# Source.net
KiCad netlist of a schematic drawn in Altium Designer
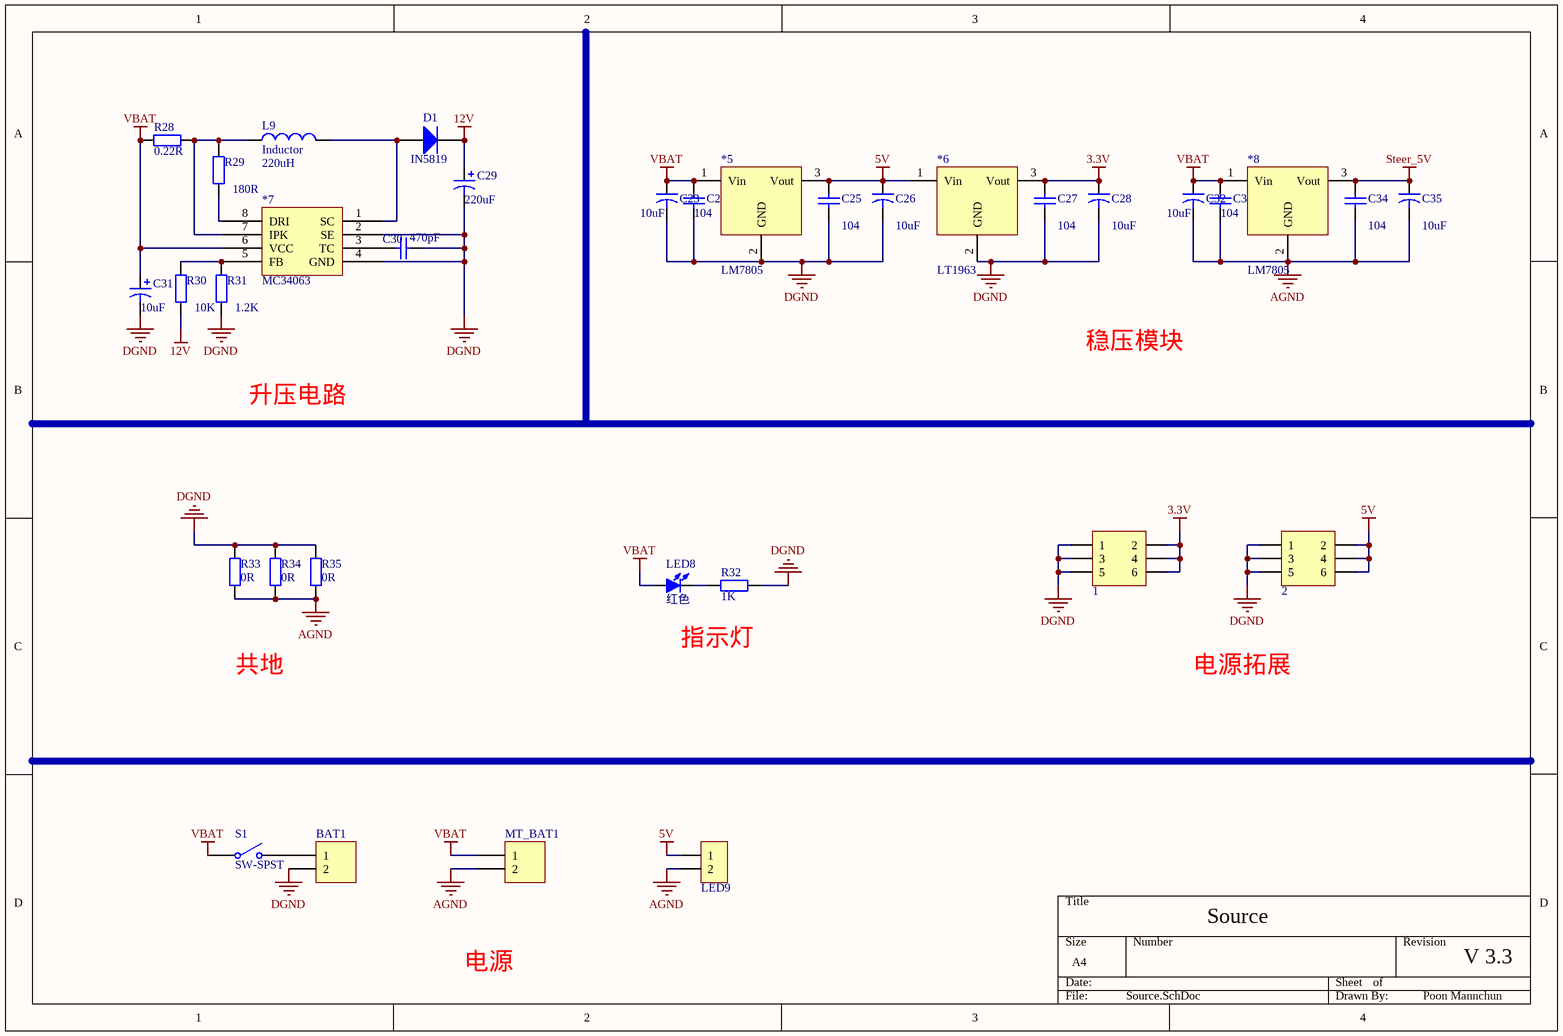
[diagram p0: Source.SchDoc]

(export (version "E")
  (design (tool "Eeschema 10.0.6"))
  (components
    (comp (ref "*5") (value "LM7805") (footprint "SOT223_N") (libsource (lib "LongMen") (part "LM2940")))
    (comp (ref "*6") (value "LT1963") (footprint "SOT223_N") (libsource (lib "LongMen") (part "LM2940")))
    (comp (ref "*7") (value "MC34063") (footprint "SOP8_N") (libsource (lib "MIC5219") (part "MC34063")))
    (comp (ref "*8") (value "LM7805") (footprint "SOT223_N") (libsource (lib "LongMen") (part "LM2940")))
    (comp (ref "1")
      (value "Header3X2")
      (footprint "HDR-3X2")
      (description "3*2P接插件")
      (fields (field (name "版权归属") "源创客"))
      (libsource (lib "接插件") (part "Header 3X2"))
    )
    (comp (ref "2")
      (value "Header3X2")
      (footprint "HDR-3X2")
      (description "3*2P接插件")
      (fields (field (name "版权归属") "源创客"))
      (libsource (lib "接插件") (part "Header 3X2"))
    )
    (comp (ref "BAT1")
      (value "Header 2")
      (footprint "SW - duplicate")
      (description "Header, 2-Pin")
      (fields (field (name "PUBLISHER") "Altium Limited"))
      (libsource (lib "PROJECT") (part "Header 2"))
    )
    (comp (ref "C23")
      (value "10uF")
      (footprint "CD A(3216)")
      (description "Capacitor")
      (fields (field (name "Comment") "Cap2") (field (name "PUBLISHER") "Altium Limited"))
      (libsource (lib "Miscellaneous Devices") (part "Cap2"))
    )
    (comp (ref "C24")
      (value "104")
      (footprint "C 0805_L")
      (description "Capacitor")
      (fields (field (name "PUBLISHER") "Altium Limited"))
      (libsource (lib "Miscellaneous Devices") (part "Cap"))
    )
    (comp (ref "C25")
      (value "104")
      (footprint "C 0805_L")
      (description "Capacitor")
      (fields (field (name "PUBLISHER") "Altium Limited"))
      (libsource (lib "Miscellaneous Devices") (part "Cap"))
    )
    (comp (ref "C26")
      (value "10uF")
      (footprint "CD A(3216)")
      (description "Capacitor")
      (fields (field (name "Comment") "Cap2") (field (name "PUBLISHER") "Altium Limited"))
      (libsource (lib "Miscellaneous Devices") (part "Cap2"))
    )
    (comp (ref "C27")
      (value "104")
      (footprint "C 0805_L")
      (description "Capacitor")
      (fields (field (name "PUBLISHER") "Altium Limited"))
      (libsource (lib "Miscellaneous Devices") (part "Cap"))
    )
    (comp (ref "C28")
      (value "10uF")
      (footprint "CD A(3216)")
      (description "Capacitor")
      (fields (field (name "Comment") "Cap2") (field (name "PUBLISHER") "Altium Limited"))
      (libsource (lib "Miscellaneous Devices") (part "Cap2"))
    )
    (comp (ref "C29")
      (value "220uF")
      (footprint "CD B(3528)")
      (description "Polarized Capacitor (Radial)")
      (fields (field (name "Comment") "Cap Pol1") (field (name "PUBLISHER") "Altium Limited"))
      (libsource (lib "Miscellaneous Devices") (part "Cap Pol1"))
    )
    (comp (ref "C30")
      (value "470pF")
      (footprint "C 0805_L")
      (description "Capacitor")
      (fields (field (name "Comment") "Cap") (field (name "PUBLISHER") "Altium Limited"))
      (libsource (lib "Miscellaneous Devices") (part "Cap"))
    )
    (comp (ref "C31")
      (value "10uF")
      (footprint "CD A(3216)")
      (description "Polarized Capacitor (Radial)")
      (fields (field (name "Comment") "Cap Pol1") (field (name "PUBLISHER") "Altium Limited"))
      (libsource (lib "Miscellaneous Devices") (part "Cap Pol1"))
    )
    (comp (ref "C32")
      (value "10uF")
      (footprint "CD A(3216)")
      (description "Capacitor")
      (fields (field (name "Comment") "Cap2") (field (name "PUBLISHER") "Altium Limited"))
      (libsource (lib "Miscellaneous Devices") (part "Cap2"))
    )
    (comp (ref "C33")
      (value "104")
      (footprint "C 0805_L")
      (description "Capacitor")
      (fields (field (name "PUBLISHER") "Altium Limited"))
      (libsource (lib "Miscellaneous Devices") (part "Cap"))
    )
    (comp (ref "C34")
      (value "104")
      (footprint "C 0805_L")
      (description "Capacitor")
      (fields (field (name "PUBLISHER") "Altium Limited"))
      (libsource (lib "Miscellaneous Devices") (part "Cap"))
    )
    (comp (ref "C35")
      (value "10uF")
      (footprint "CD A(3216)")
      (description "Capacitor")
      (fields (field (name "Comment") "Cap2") (field (name "PUBLISHER") "Altium Limited"))
      (libsource (lib "Miscellaneous Devices") (part "Cap2"))
    )
    (comp (ref "D1")
      (value "IN5819")
      (footprint "SMA")
      (description "Default Diode")
      (fields (field (name "PUBLISHER") "Altium Limited"))
      (libsource (lib "Miscellaneous Devices") (part "Diode"))
    )
    (comp (ref "L9")
      (value "Inductor")
      (footprint "CDRH124")
      (fields (field (name "ALTIUM_VALUE") "220uH") (field (name "PUBLISHER") "Altium Limited"))
      (libsource (lib "Miscellaneous Devices") (part "Inductor"))
    )
    (comp (ref "LED8")
      (value "红色")
      (footprint "LED 0805R")
      (description "贴片LED")
      (fields (field (name "版权归属") "源创客"))
      (libsource (lib "LED") (part "LED-SMD"))
    )
    (comp (ref "LED9")
      (value "HDR-1X2")
      (footprint "HDR-1X2")
      (description "2P接插件")
      (fields (field (name "版权归属") "源创客"))
      (libsource (lib "接插件") (part "Header 2"))
    )
    (comp (ref "MT_BAT1")
      (value "Header 2")
      (footprint "SW - duplicate")
      (description "Header, 2-Pin")
      (fields (field (name "PUBLISHER") "Altium Limited"))
      (libsource (lib "PROJECT") (part "Header 2"))
    )
    (comp (ref "R28")
      (value "0.22R")
      (footprint "R 0805_L")
      (description "Resistor")
      (fields (field (name "Comment") "Res2") (field (name "PUBLISHER") "Altium Limited"))
      (libsource (lib "") (part "Res2_2"))
    )
    (comp (ref "R29")
      (value "180R")
      (footprint "R 0805_L")
      (description "Resistor")
      (fields (field (name "Comment") "Res2") (field (name "PUBLISHER") "Altium Limited"))
      (libsource (lib "") (part "Res2_1"))
    )
    (comp (ref "R30")
      (value "10K")
      (footprint "R 0805_L")
      (description "Resistor")
      (fields (field (name "Comment") "Res2") (field (name "PUBLISHER") "Altium Limited"))
      (libsource (lib "") (part "Res2_1"))
    )
    (comp (ref "R31")
      (value "1.2K")
      (footprint "R 0805_L")
      (description "Resistor")
      (fields (field (name "Comment") "Res2") (field (name "PUBLISHER") "Altium Limited"))
      (libsource (lib "") (part "Res2_1"))
    )
    (comp (ref "R32")
      (value "1K")
      (footprint "R 0805_L")
      (description "Resistor")
      (fields (field (name "PUBLISHER") "Altium Limited"))
      (libsource (lib "6-MK60DN512VLL10核心板") (part "Res2"))
    )
    (comp (ref "R33")
      (value "0R")
      (footprint "R 0805_L")
      (description "Resistor")
      (fields (field (name "Comment") "Res2") (field (name "PUBLISHER") "Altium Limited"))
      (libsource (lib "Miscellaneous Devices") (part "Res2"))
    )
    (comp (ref "R34")
      (value "0R")
      (footprint "R 0805_L")
      (description "Resistor")
      (fields (field (name "Comment") "Res2") (field (name "PUBLISHER") "Altium Limited"))
      (libsource (lib "Miscellaneous Devices") (part "Res2"))
    )
    (comp (ref "R35")
      (value "0R")
      (footprint "R 0805_L")
      (description "Resistor")
      (fields (field (name "Comment") "Res2") (field (name "PUBLISHER") "Altium Limited"))
      (libsource (lib "Miscellaneous Devices") (part "Res2"))
    )
    (comp (ref "S1")
      (value "SW-SPST")
      (footprint "MTS-10x")
      (description "Single-Pole, Single-Throw Switch")
      (fields (field (name "PUBLISHER") "Altium Limited"))
      (libsource (lib "Miscellaneous Devices") (part "SW-SPST"))
    )
  )
  (nets
    (net (code "1") (name "3.3V") (class "Default")
      (node (ref "*6") (pin "3") (pinfunction "Vout_3") (pintype "passive"))
      (node (ref "1") (pin "2") (pinfunction "2_2") (pintype "passive"))
      (node (ref "1") (pin "4") (pinfunction "4_4") (pintype "passive"))
      (node (ref "1") (pin "6") (pinfunction "6_6") (pintype "passive"))
      (node (ref "C27") (pin "2") (pinfunction "2_2") (pintype "passive"))
      (node (ref "C28") (pin "1") (pinfunction "1_1") (pintype "passive"))
    )
    (net (code "2") (name "5V") (class "Default")
      (node (ref "*5") (pin "3") (pinfunction "Vout_3") (pintype "passive"))
      (node (ref "*6") (pin "1") (pinfunction "Vin_1") (pintype "passive"))
      (node (ref "2") (pin "2") (pinfunction "2_2") (pintype "passive"))
      (node (ref "2") (pin "4") (pinfunction "4_4") (pintype "passive"))
      (node (ref "2") (pin "6") (pinfunction "6_6") (pintype "passive"))
      (node (ref "C25") (pin "2") (pinfunction "2_2") (pintype "passive"))
      (node (ref "C26") (pin "1") (pinfunction "1_1") (pintype "passive"))
      (node (ref "LED9") (pin "1") (pinfunction "1_1") (pintype "passive"))
    )
    (net (code "3") (name "12V") (class "Default")
      (node (ref "C29") (pin "1") (pinfunction "1_1") (pintype "passive"))
      (node (ref "D1") (pin "2") (pinfunction "K_2") (pintype "passive"))
      (node (ref "R30") (pin "1") (pinfunction "1_1") (pintype "passive"))
    )
    (net (code "4") (name "AGND") (class "Default")
      (node (ref "*8") (pin "2") (pinfunction "GND_2") (pintype "passive"))
      (node (ref "C32") (pin "2") (pinfunction "2_2") (pintype "passive"))
      (node (ref "C33") (pin "1") (pinfunction "1_1") (pintype "passive"))
      (node (ref "C34") (pin "1") (pinfunction "1_1") (pintype "passive"))
      (node (ref "C35") (pin "2") (pinfunction "2_2") (pintype "passive"))
      (node (ref "LED9") (pin "2") (pinfunction "2_2") (pintype "passive"))
      (node (ref "MT_BAT1") (pin "2") (pinfunction "2_2") (pintype "passive"))
      (node (ref "R33") (pin "2") (pinfunction "2_2") (pintype "passive"))
      (node (ref "R34") (pin "2") (pinfunction "2_2") (pintype "passive"))
      (node (ref "R35") (pin "2") (pinfunction "2_2") (pintype "passive"))
    )
    (net (code "5") (name "DGND") (class "Default")
      (node (ref "*5") (pin "2") (pinfunction "GND_2") (pintype "passive"))
      (node (ref "*6") (pin "2") (pinfunction "GND_2") (pintype "passive"))
      (node (ref "*7") (pin "2") (pinfunction "SE_2") (pintype "passive"))
      (node (ref "*7") (pin "4") (pinfunction "GND_4") (pintype "passive"))
      (node (ref "1") (pin "1") (pinfunction "1_1") (pintype "passive"))
      (node (ref "1") (pin "3") (pinfunction "3_3") (pintype "passive"))
      (node (ref "1") (pin "5") (pinfunction "5_5") (pintype "passive"))
      (node (ref "2") (pin "1") (pinfunction "1_1") (pintype "passive"))
      (node (ref "2") (pin "3") (pinfunction "3_3") (pintype "passive"))
      (node (ref "2") (pin "5") (pinfunction "5_5") (pintype "passive"))
      (node (ref "BAT1") (pin "2") (pinfunction "2_2") (pintype "passive"))
      (node (ref "C23") (pin "2") (pinfunction "2_2") (pintype "passive"))
      (node (ref "C24") (pin "1") (pinfunction "1_1") (pintype "passive"))
      (node (ref "C25") (pin "1") (pinfunction "1_1") (pintype "passive"))
      (node (ref "C26") (pin "2") (pinfunction "2_2") (pintype "passive"))
      (node (ref "C27") (pin "1") (pinfunction "1_1") (pintype "passive"))
      (node (ref "C28") (pin "2") (pinfunction "2_2") (pintype "passive"))
      (node (ref "C29") (pin "2") (pinfunction "2_2") (pintype "passive"))
      (node (ref "C30") (pin "2") (pinfunction "2_2") (pintype "passive"))
      (node (ref "C31") (pin "2") (pinfunction "2_2") (pintype "passive"))
      (node (ref "R31") (pin "1") (pinfunction "1_1") (pintype "passive"))
      (node (ref "R32") (pin "2") (pinfunction "2_2") (pintype "passive"))
      (node (ref "R33") (pin "1") (pinfunction "1_1") (pintype "passive"))
      (node (ref "R34") (pin "1") (pinfunction "1_1") (pintype "passive"))
      (node (ref "R35") (pin "1") (pinfunction "1_1") (pintype "passive"))
    )
    (net (code "6") (name "Net-(*7-DRI)") (class "Default")
      (node (ref "*7") (pin "8") (pinfunction "DRI_8") (pintype "passive"))
      (node (ref "R29") (pin "1") (pinfunction "1_1") (pintype "passive"))
    )
    (net (code "7") (name "Net-(*7-FB)") (class "Default")
      (node (ref "*7") (pin "5") (pinfunction "FB_5") (pintype "passive"))
      (node (ref "R30") (pin "2") (pinfunction "2_2") (pintype "passive"))
      (node (ref "R31") (pin "2") (pinfunction "2_2") (pintype "passive"))
    )
    (net (code "8") (name "Net-(*7-IPK)") (class "Default")
      (node (ref "*7") (pin "7") (pinfunction "IPK_7") (pintype "passive"))
      (node (ref "L9") (pin "1") (pinfunction "1_1") (pintype "passive"))
      (node (ref "R28") (pin "1") (pinfunction "1_1") (pintype "passive"))
      (node (ref "R29") (pin "2") (pinfunction "2_2") (pintype "passive"))
    )
    (net (code "9") (name "Net-(*7-SC)") (class "Default")
      (node (ref "*7") (pin "1") (pinfunction "SC_1") (pintype "passive"))
      (node (ref "D1") (pin "1") (pinfunction "A_1") (pintype "passive"))
      (node (ref "L9") (pin "2") (pinfunction "2_2") (pintype "passive"))
    )
    (net (code "10") (name "Net-(*7-TC)") (class "Default")
      (node (ref "*7") (pin "3") (pinfunction "TC_3") (pintype "passive"))
      (node (ref "C30") (pin "1") (pinfunction "1_1") (pintype "passive"))
    )
    (net (code "11") (name "Net-(LED8-K)") (class "Default")
      (node (ref "LED8") (pin "2") (pinfunction "K_2") (pintype "passive"))
      (node (ref "R32") (pin "1") (pinfunction "1_1") (pintype "passive"))
    )
    (net (code "12") (name "Net-(S1-NO)") (class "Default")
      (node (ref "BAT1") (pin "1") (pinfunction "1_1") (pintype "passive"))
      (node (ref "S1") (pin "2") (pinfunction "NO_2") (pintype "passive"))
    )
    (net (code "13") (name "Steer_5V") (class "Default")
      (node (ref "*8") (pin "3") (pinfunction "Vout_3") (pintype "passive"))
      (node (ref "C34") (pin "2") (pinfunction "2_2") (pintype "passive"))
      (node (ref "C35") (pin "1") (pinfunction "1_1") (pintype "passive"))
    )
    (net (code "14") (name "VBAT") (class "Default")
      (node (ref "*5") (pin "1") (pinfunction "Vin_1") (pintype "passive"))
      (node (ref "*7") (pin "6") (pinfunction "VCC_6") (pintype "passive"))
      (node (ref "*8") (pin "1") (pinfunction "Vin_1") (pintype "passive"))
      (node (ref "C23") (pin "1") (pinfunction "1_1") (pintype "passive"))
      (node (ref "C24") (pin "2") (pinfunction "2_2") (pintype "passive"))
      (node (ref "C31") (pin "1") (pinfunction "1_1") (pintype "passive"))
      (node (ref "C32") (pin "1") (pinfunction "1_1") (pintype "passive"))
      (node (ref "C33") (pin "2") (pinfunction "2_2") (pintype "passive"))
      (node (ref "LED8") (pin "1") (pinfunction "A_1") (pintype "passive"))
      (node (ref "MT_BAT1") (pin "1") (pinfunction "1_1") (pintype "passive"))
      (node (ref "R28") (pin "2") (pinfunction "2_2") (pintype "passive"))
      (node (ref "S1") (pin "1") (pinfunction "COMMON_1") (pintype "passive"))
    )
  )
)
